# radio_module_V2_0.net
KiCad netlist of a schematic drawn in EAGLE
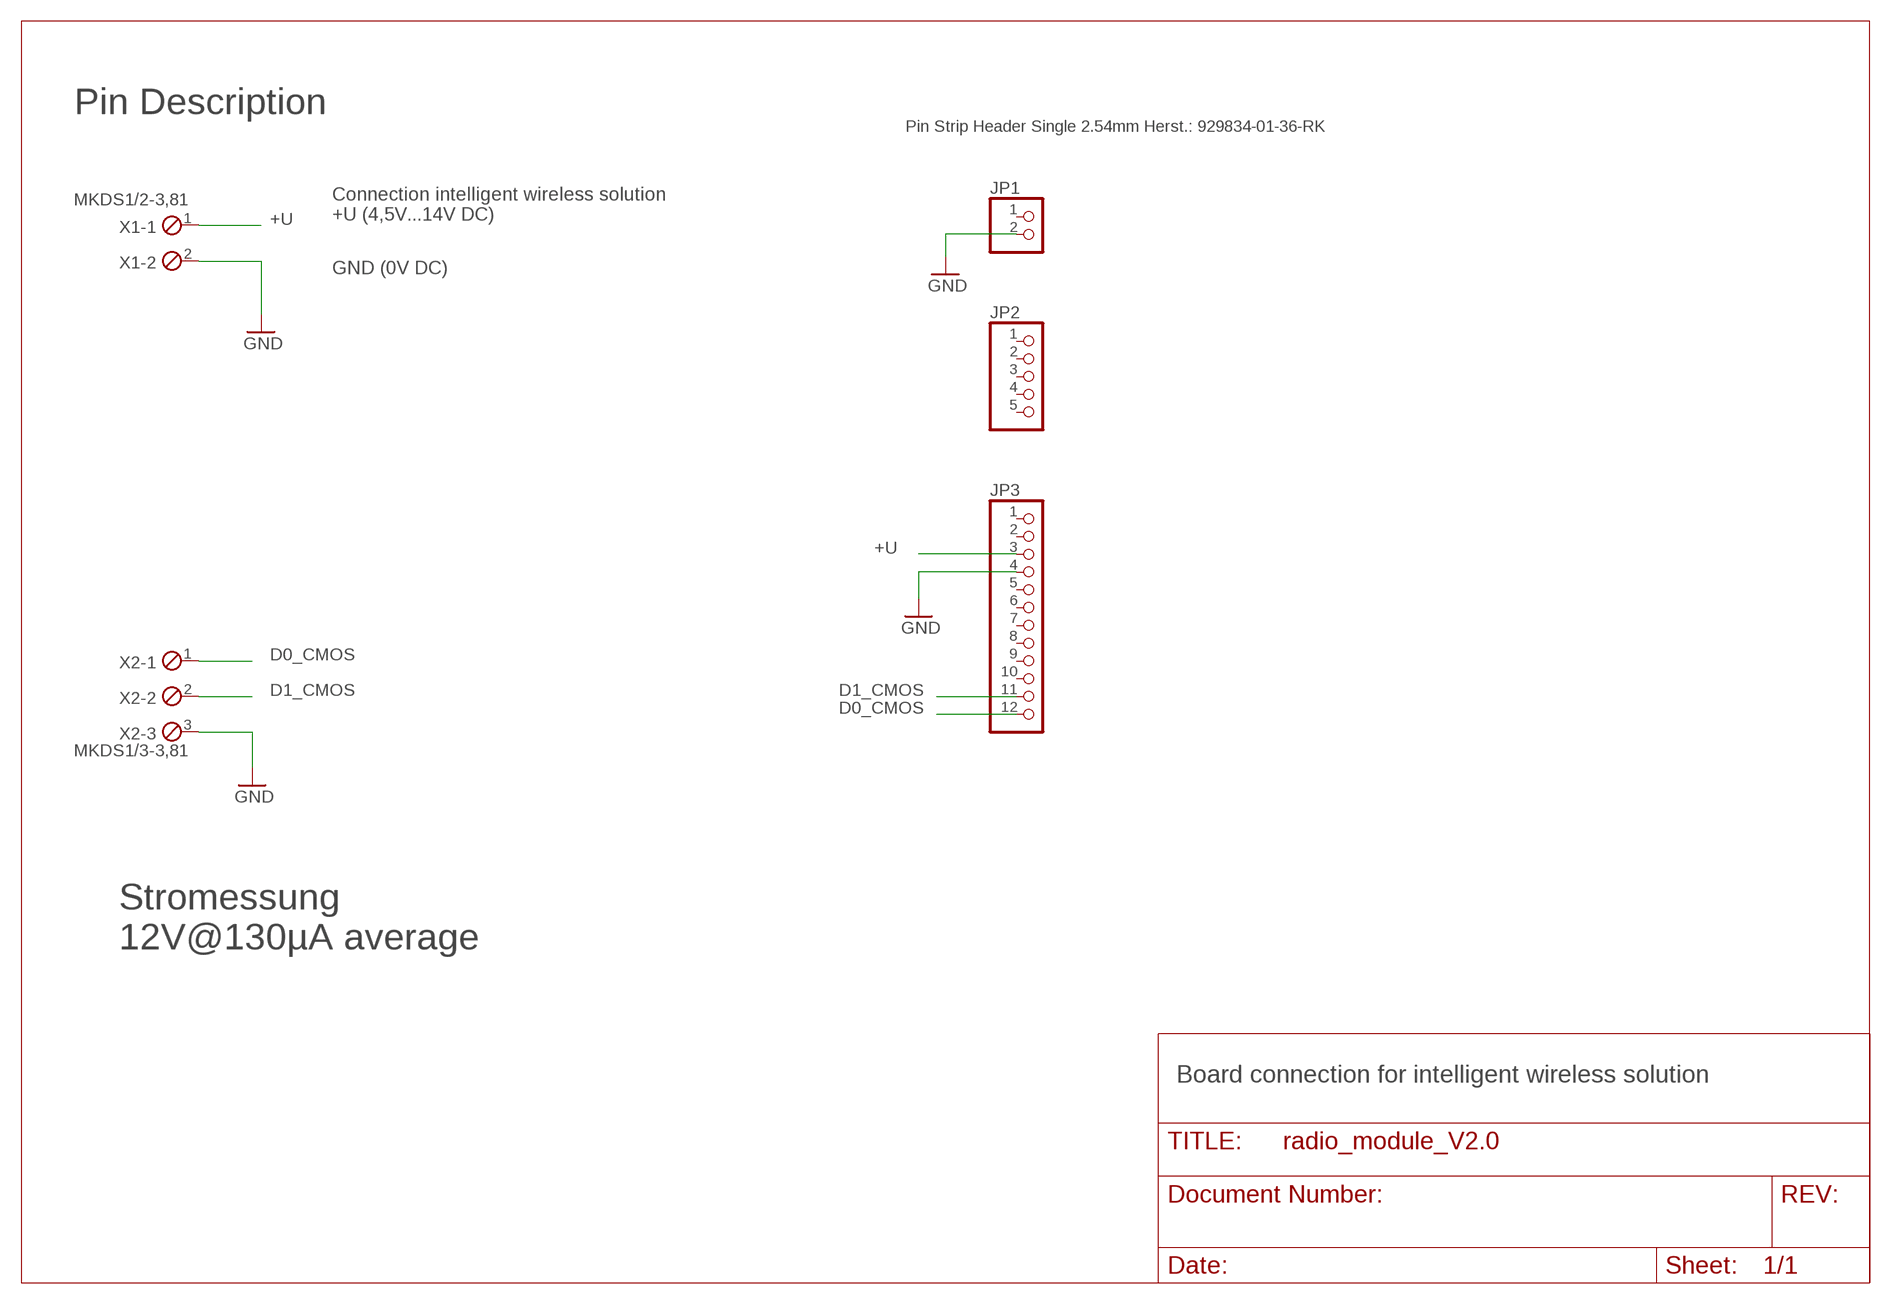
[diagram p0: schematic, sheet 1]

(export (version "E")
  (design (tool "Eeschema 10.0.6"))
  (components
    (comp (ref "JP1")
      (value "PINHD-1X2")
      (footprint "eagle-import:1X02")
      (libsource (lib "eagle-import") (part "PINHD-1X2"))
    )
    (comp (ref "JP2")
      (value "PINHD-1X5")
      (footprint "eagle-import:1X05")
      (libsource (lib "eagle-import") (part "PINHD-1X5"))
    )
    (comp (ref "JP3")
      (value "PINHD-1X12")
      (footprint "eagle-import:1X12")
      (libsource (lib "eagle-import") (part "PINHD-1X12"))
    )
    (comp (ref "X1")
      (value "MKDS1/2-3,81")
      (footprint "eagle-import:2POL381")
      (libsource (lib "eagle-import") (part "MKDS1/2-3,81"))
    )
    (comp (ref "X2")
      (value "MKDS1/3-3,81")
      (footprint "eagle-import:3POL381")
      (libsource (lib "eagle-import") (part "MKDS1/3-3,81"))
    )
  )
  (nets
    (net (code "1") (name "/+U") (class "Default")
      (node (ref "JP3") (pin "3") (pinfunction "3_3") (pintype "passive"))
      (node (ref "X1") (pin "1") (pinfunction "1_1") (pintype "passive"))
    )
    (net (code "2") (name "/D0_CMOS") (class "Default")
      (node (ref "JP3") (pin "12") (pinfunction "12_12") (pintype "passive"))
      (node (ref "X2") (pin "1") (pinfunction "1_1") (pintype "passive"))
    )
    (net (code "3") (name "/D1_CMOS") (class "Default")
      (node (ref "JP3") (pin "11") (pinfunction "11_11") (pintype "passive"))
      (node (ref "X2") (pin "2") (pinfunction "1_2") (pintype "passive"))
    )
    (net (code "4") (name "GND") (class "Default")
      (node (ref "JP1") (pin "2") (pinfunction "2_2") (pintype "passive"))
      (node (ref "JP3") (pin "4") (pinfunction "4_4") (pintype "passive"))
      (node (ref "X1") (pin "2") (pinfunction "1_2") (pintype "passive"))
      (node (ref "X2") (pin "3") (pinfunction "1_3") (pintype "passive"))
    )
    (net (code "5") (name "unconnected-(JP1-Pad1)") (class "Default")
      (node (ref "JP1") (pin "1") (pinfunction "1_1") (pintype "passive"))
    )
    (net (code "6") (name "unconnected-(JP2-Pad1)") (class "Default")
      (node (ref "JP2") (pin "1") (pinfunction "1_1") (pintype "passive"))
    )
    (net (code "7") (name "unconnected-(JP2-Pad2)") (class "Default")
      (node (ref "JP2") (pin "2") (pinfunction "2_2") (pintype "passive"))
    )
    (net (code "8") (name "unconnected-(JP2-Pad3)") (class "Default")
      (node (ref "JP2") (pin "3") (pinfunction "3_3") (pintype "passive"))
    )
    (net (code "9") (name "unconnected-(JP2-Pad4)") (class "Default")
      (node (ref "JP2") (pin "4") (pinfunction "4_4") (pintype "passive"))
    )
    (net (code "10") (name "unconnected-(JP2-Pad5)") (class "Default")
      (node (ref "JP2") (pin "5") (pinfunction "5_5") (pintype "passive"))
    )
    (net (code "11") (name "unconnected-(JP3-Pad1)") (class "Default")
      (node (ref "JP3") (pin "1") (pinfunction "1_1") (pintype "passive"))
    )
    (net (code "12") (name "unconnected-(JP3-Pad2)") (class "Default")
      (node (ref "JP3") (pin "2") (pinfunction "2_2") (pintype "passive"))
    )
    (net (code "13") (name "unconnected-(JP3-Pad5)") (class "Default")
      (node (ref "JP3") (pin "5") (pinfunction "5_5") (pintype "passive"))
    )
    (net (code "14") (name "unconnected-(JP3-Pad6)") (class "Default")
      (node (ref "JP3") (pin "6") (pinfunction "6_6") (pintype "passive"))
    )
    (net (code "15") (name "unconnected-(JP3-Pad7)") (class "Default")
      (node (ref "JP3") (pin "7") (pinfunction "7_7") (pintype "passive"))
    )
    (net (code "16") (name "unconnected-(JP3-Pad8)") (class "Default")
      (node (ref "JP3") (pin "8") (pinfunction "8_8") (pintype "passive"))
    )
    (net (code "17") (name "unconnected-(JP3-Pad9)") (class "Default")
      (node (ref "JP3") (pin "9") (pinfunction "9_9") (pintype "passive"))
    )
    (net (code "18") (name "unconnected-(JP3-Pad10)") (class "Default")
      (node (ref "JP3") (pin "10") (pinfunction "10_10") (pintype "passive"))
    )
  )
)
